# RasberryPi5.net
KiCad netlist of a schematic drawn in Altium Designer
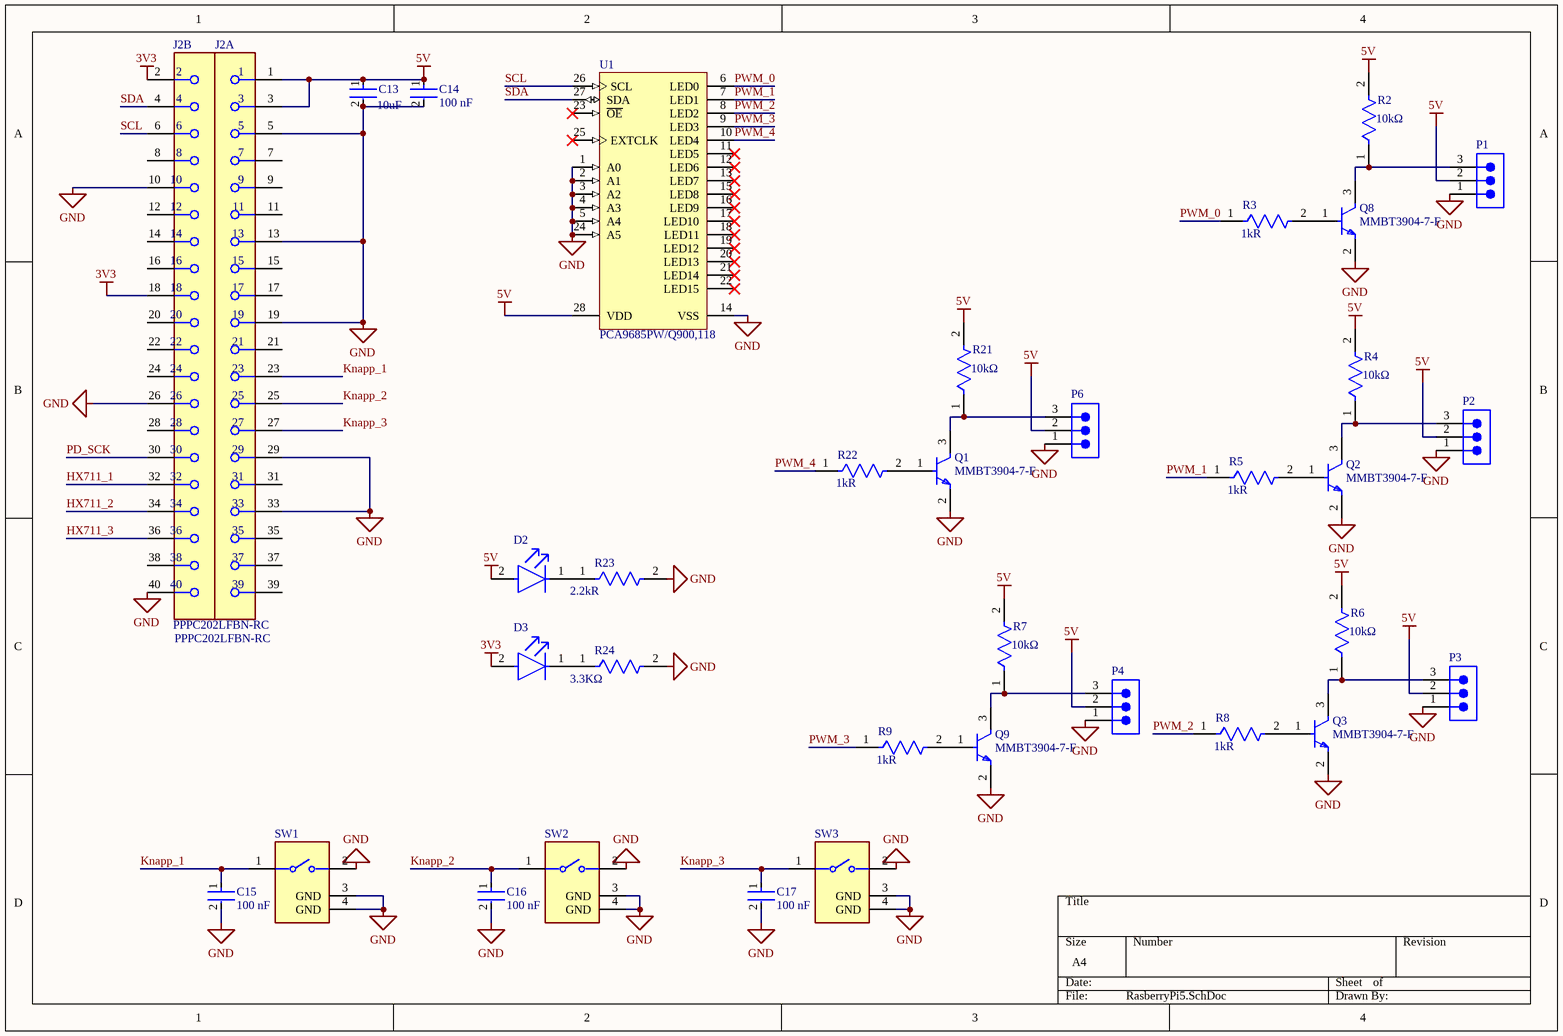
[diagram p0: RasberryPi5.SchDoc]

(export (version "E")
  (design (tool "Eeschema 10.0.6"))
  (components
    (comp (ref "C13")
      (value "10uF")
      (footprint "FP-GRM18-0_15-MFG")
      (description "CAP CER 10UF 10V X5R 0603")
      (fields
        (field (name "OCTOPART") "https://octopart.com/grm188r61a106ke69d-murata-22851381")
        (field (name "MANUFACTURER PART NUMBER") "GRM188R61A106KE69D")
      )
      (libsource (lib "Altium Content Vault") (part "11868f565c42a9108669ba33697ecf6"))
    )
    (comp (ref "C14")
      (value "100 nF")
      (footprint "FP-CC0603-DA-MFG")
      (description "CC0603 100 nF X7R 10.00% 25 V")
      (fields (field (name "VOLTAGE") "25 V") (field (name "MANUFACTURER PART NUMBER") "CC0603KPX7R8BB104"))
      (libsource (lib "Altium Content Vault") (part "11868f565c42a9108669ba33697ecf6"))
    )
    (comp (ref "C15")
      (value "100 nF")
      (footprint "FP-CC0603-DA-MFG")
      (description "CC0603 100 nF X7R 10.00% 25 V")
      (fields (field (name "VOLTAGE") "25 V") (field (name "MANUFACTURER PART NUMBER") "CC0603KPX7R8BB104"))
      (libsource (lib "Altium Content Vault") (part "11868f565c42a9108669ba33697ecf6"))
    )
    (comp (ref "C16")
      (value "100 nF")
      (footprint "FP-CC0603-DA-MFG")
      (description "CC0603 100 nF X7R 10.00% 25 V")
      (fields (field (name "VOLTAGE") "25 V") (field (name "MANUFACTURER PART NUMBER") "CC0603KPX7R8BB104"))
      (libsource (lib "Altium Content Vault") (part "11868f565c42a9108669ba33697ecf6"))
    )
    (comp (ref "C17")
      (value "100 nF")
      (footprint "FP-CC0603-DA-MFG")
      (description "CC0603 100 nF X7R 10.00% 25 V")
      (fields (field (name "VOLTAGE") "25 V") (field (name "MANUFACTURER PART NUMBER") "CC0603KPX7R8BB104"))
      (libsource (lib "Altium Content Vault") (part "11868f565c42a9108669ba33697ecf6"))
    )
    (comp (ref "D2")
      (value "LTST-C193KGKT-5A")
      (footprint "FP-LTST-C193KGKT-5A-MFG")
      (description "LED GREEN CLEAR CHIP SMD")
      (libsource (lib "Altium Content Vault") (part "8706943c75ba83719d021d2fdc84c58"))
    )
    (comp (ref "D3")
      (value "LTST-C193KGKT-5A")
      (footprint "FP-LTST-C193KGKT-5A-MFG")
      (description "LED GREEN CLEAR CHIP SMD")
      (libsource (lib "Altium Content Vault") (part "8706943c75ba83719d021d2fdc84c58"))
    )
    (comp (ref "J2")
      (value "PPPC202LFBN-RC")
      (footprint "FP-PPPC202LFBN-RC-MFG")
      (description "PPPC202LFBN-RC Female, 40C, Straight, .100\"CC; 3.20mm Tail, No Mt.; PBT, Phos Bronze, 105 C")
      (libsource (lib "Altium Content Vault") (part "e49c40d8a4b72700ef4f9e86232dadc"))
    )
    (comp (ref "P1")
      (value "MTSW-103-08-L-S-229-RA")
      (footprint "SMTC-MTSW-103-08-X-S-229-RA")
      (fields (field (name "MANUFACTURER") "Samtec"))
      (libsource (lib "Altium Content Vault") (part "SMTC-MTSW-103-08-X-S-229-RA"))
    )
    (comp (ref "P2")
      (value "MTSW-103-08-L-S-229-RA")
      (footprint "SMTC-MTSW-103-08-X-S-229-RA")
      (fields (field (name "MANUFACTURER") "Samtec"))
      (libsource (lib "Altium Content Vault") (part "SMTC-MTSW-103-08-X-S-229-RA"))
    )
    (comp (ref "P3")
      (value "MTSW-103-08-L-S-229-RA")
      (footprint "SMTC-MTSW-103-08-X-S-229-RA")
      (fields (field (name "MANUFACTURER") "Samtec"))
      (libsource (lib "Altium Content Vault") (part "SMTC-MTSW-103-08-X-S-229-RA"))
    )
    (comp (ref "P4")
      (value "MTSW-103-08-L-S-229-RA")
      (footprint "SMTC-MTSW-103-08-X-S-229-RA")
      (fields (field (name "MANUFACTURER") "Samtec"))
      (libsource (lib "Altium Content Vault") (part "SMTC-MTSW-103-08-X-S-229-RA"))
    )
    (comp (ref "P6")
      (value "MTSW-103-08-L-S-229-RA")
      (footprint "SMTC-MTSW-103-08-X-S-229-RA")
      (fields (field (name "MANUFACTURER") "Samtec"))
      (libsource (lib "Altium Content Vault") (part "SMTC-MTSW-103-08-X-S-229-RA"))
    )
    (comp (ref "Q1")
      (value "MMBT3904-7-F")
      (footprint "FP-SOT23-IPC_A")
      (description "TRANS NPN 40V 0.2A SMD SOT23-3")
      (libsource (lib "Altium Content Vault") (part "b44e953556f554d0102664c7d152cb4"))
    )
    (comp (ref "Q2")
      (value "MMBT3904-7-F")
      (footprint "FP-SOT23-IPC_A")
      (description "TRANS NPN 40V 0.2A SMD SOT23-3")
      (libsource (lib "Altium Content Vault") (part "b44e953556f554d0102664c7d152cb4"))
    )
    (comp (ref "Q3")
      (value "MMBT3904-7-F")
      (footprint "FP-SOT23-IPC_A")
      (description "TRANS NPN 40V 0.2A SMD SOT23-3")
      (libsource (lib "Altium Content Vault") (part "b44e953556f554d0102664c7d152cb4"))
    )
    (comp (ref "Q8")
      (value "MMBT3904-7-F")
      (footprint "FP-SOT23-IPC_A")
      (description "TRANS NPN 40V 0.2A SMD SOT23-3")
      (libsource (lib "Altium Content Vault") (part "b44e953556f554d0102664c7d152cb4"))
    )
    (comp (ref "Q9")
      (value "MMBT3904-7-F")
      (footprint "FP-SOT23-IPC_A")
      (description "TRANS NPN 40V 0.2A SMD SOT23-3")
      (libsource (lib "Altium Content Vault") (part "b44e953556f554d0102664c7d152cb4"))
    )
    (comp (ref "R2")
      (value "SG73P1JTTD1002F")
      (footprint "FP-SG73P1J-MFG")
      (description "SG73P1JTTD1002F Res Thick Film 0603 10K Ohm 1% 0.2W(1/5W) ±100ppm/C Pad SMD Automotive T/R")
      (fields (field (name "TOLERANCE") "1%") (field (name "RESISTANCE") "10kΩ"))
      (libsource (lib "Altium Content Vault") (part "1029c3af85768c4190bb7ad29bc67b5"))
    )
    (comp (ref "R3")
      (value "RK73G1JTTD1001F")
      (footprint "FP-RK73G1J-IPC_B")
      (description "1kΩ ±1% 0.1W Chip Resistor 0603 Thick Film AEC-Q200 Qualified")
      (fields (field (name "RESISTANCE") "1kR") (field (name "TOLERANCE") "1%"))
      (libsource (lib "Altium Content Vault") (part "1029c3af85768c4190bb7ad29bc67b5"))
    )
    (comp (ref "R4")
      (value "SG73P1JTTD1002F")
      (footprint "FP-SG73P1J-MFG")
      (description "SG73P1JTTD1002F Res Thick Film 0603 10K Ohm 1% 0.2W(1/5W) ±100ppm/C Pad SMD Automotive T/R")
      (fields (field (name "TOLERANCE") "1%") (field (name "RESISTANCE") "10kΩ"))
      (libsource (lib "Altium Content Vault") (part "1029c3af85768c4190bb7ad29bc67b5"))
    )
    (comp (ref "R5")
      (value "RK73G1JTTD1001F")
      (footprint "FP-RK73G1J-IPC_B")
      (description "1kΩ ±1% 0.1W Chip Resistor 0603 Thick Film AEC-Q200 Qualified")
      (fields (field (name "RESISTANCE") "1kR") (field (name "TOLERANCE") "1%"))
      (libsource (lib "Altium Content Vault") (part "1029c3af85768c4190bb7ad29bc67b5"))
    )
    (comp (ref "R6")
      (value "SG73P1JTTD1002F")
      (footprint "FP-SG73P1J-MFG")
      (description "SG73P1JTTD1002F Res Thick Film 0603 10K Ohm 1% 0.2W(1/5W) ±100ppm/C Pad SMD Automotive T/R")
      (fields (field (name "TOLERANCE") "1%") (field (name "RESISTANCE") "10kΩ"))
      (libsource (lib "Altium Content Vault") (part "1029c3af85768c4190bb7ad29bc67b5"))
    )
    (comp (ref "R7")
      (value "SG73P1JTTD1002F")
      (footprint "FP-SG73P1J-MFG")
      (description "SG73P1JTTD1002F Res Thick Film 0603 10K Ohm 1% 0.2W(1/5W) ±100ppm/C Pad SMD Automotive T/R")
      (fields (field (name "TOLERANCE") "1%") (field (name "RESISTANCE") "10kΩ"))
      (libsource (lib "Altium Content Vault") (part "1029c3af85768c4190bb7ad29bc67b5"))
    )
    (comp (ref "R8")
      (value "RK73G1JTTD1001F")
      (footprint "FP-RK73G1J-IPC_B")
      (description "1kΩ ±1% 0.1W Chip Resistor 0603 Thick Film AEC-Q200 Qualified")
      (fields (field (name "RESISTANCE") "1kR") (field (name "TOLERANCE") "1%"))
      (libsource (lib "Altium Content Vault") (part "1029c3af85768c4190bb7ad29bc67b5"))
    )
    (comp (ref "R9")
      (value "RK73G1JTTD1001F")
      (footprint "FP-RK73G1J-IPC_B")
      (description "1kΩ ±1% 0.1W Chip Resistor 0603 Thick Film AEC-Q200 Qualified")
      (fields (field (name "RESISTANCE") "1kR") (field (name "TOLERANCE") "1%"))
      (libsource (lib "Altium Content Vault") (part "1029c3af85768c4190bb7ad29bc67b5"))
    )
    (comp (ref "R21")
      (value "SG73P1JTTD1002F")
      (footprint "FP-SG73P1J-MFG")
      (description "SG73P1JTTD1002F Res Thick Film 0603 10K Ohm 1% 0.2W(1/5W) ±100ppm/C Pad SMD Automotive T/R")
      (fields (field (name "TOLERANCE") "1%") (field (name "RESISTANCE") "10kΩ"))
      (libsource (lib "Altium Content Vault") (part "1029c3af85768c4190bb7ad29bc67b5"))
    )
    (comp (ref "R22")
      (value "RK73G1JTTD1001F")
      (footprint "FP-RK73G1J-IPC_B")
      (description "1kΩ ±1% 0.1W Chip Resistor 0603 Thick Film AEC-Q200 Qualified")
      (fields (field (name "RESISTANCE") "1kR") (field (name "TOLERANCE") "1%"))
      (libsource (lib "Altium Content Vault") (part "1029c3af85768c4190bb7ad29bc67b5"))
    )
    (comp (ref "R23")
      (value "RC1608J222CS")
      (footprint "FP-RC1608-IPC_C")
      (description "Res Thick Film 0603 2.2kΩ 5% 0.1W ±100ppm/°C Molded SMD T/R")
      (fields (field (name "RESISTANCE") "2.2kR") (field (name "TOLERANCE") "5%"))
      (libsource (lib "Altium Content Vault") (part "1029c3af85768c4190bb7ad29bc67b5"))
    )
    (comp (ref "R24")
      (value "3.3KΩ")
      (footprint "FP-CRGCQ0603-IPC_C")
      (description "CRGCQ 0603 3K3 5%")
      (fields (field (name "TOLERANCE") "0.05") (field (name "MANUFACTURER") "TE Connectivity"))
      (libsource (lib "Altium Content Vault") (part "1029c3af85768c4190bb7ad29bc67b5"))
    )
    (comp (ref "SW1")
      (value "B3F-3122")
      (footprint "FP-B3F-3122-MFG")
      (description "SWITCH TACTILE SPST-NO 0.05A 24V")
      (libsource (lib "Altium Content Vault") (part "05c531d4b500f7e9514fa3f65f375ae"))
    )
    (comp (ref "SW2")
      (value "B3F-3122")
      (footprint "FP-B3F-3122-MFG")
      (description "SWITCH TACTILE SPST-NO 0.05A 24V")
      (libsource (lib "Altium Content Vault") (part "05c531d4b500f7e9514fa3f65f375ae"))
    )
    (comp (ref "SW3")
      (value "B3F-3122")
      (footprint "FP-B3F-3122-MFG")
      (description "SWITCH TACTILE SPST-NO 0.05A 24V")
      (libsource (lib "Altium Content Vault") (part "05c531d4b500f7e9514fa3f65f375ae"))
    )
    (comp (ref "U1")
      (value "PCA9685PW/Q900,118")
      (footprint "SOT361-1_V")
      (fields (field (name "PARTNUMBER") "PCA9685"))
      (libsource (lib "Altium Content Vault") (part "NXP-PCA9685-SOT361-1"))
    )
  )
  (nets
    (net (code "1") (name "/HX711_1") (class "Default")
      (node (ref "J2") (pin "32") (pinfunction "32_32") (pintype "passive"))
    )
    (net (code "2") (name "/HX711_2") (class "Default")
      (node (ref "J2") (pin "34") (pinfunction "34_34") (pintype "passive"))
    )
    (net (code "3") (name "/HX711_3") (class "Default")
      (node (ref "J2") (pin "36") (pinfunction "36_36") (pintype "passive"))
    )
    (net (code "4") (name "/Knapp_1") (class "Default")
      (node (ref "C15") (pin "1") (pinfunction "1_1") (pintype "passive"))
      (node (ref "J2") (pin "23") (pinfunction "23_23") (pintype "passive"))
      (node (ref "SW1") (pin "1") (pinfunction "1_1") (pintype "passive"))
    )
    (net (code "5") (name "/Knapp_2") (class "Default")
      (node (ref "C16") (pin "1") (pinfunction "1_1") (pintype "passive"))
      (node (ref "J2") (pin "25") (pinfunction "25_25") (pintype "passive"))
      (node (ref "SW2") (pin "1") (pinfunction "1_1") (pintype "passive"))
    )
    (net (code "6") (name "/Knapp_3") (class "Default")
      (node (ref "C17") (pin "1") (pinfunction "1_1") (pintype "passive"))
      (node (ref "J2") (pin "27") (pinfunction "27_27") (pintype "passive"))
      (node (ref "SW3") (pin "1") (pinfunction "1_1") (pintype "passive"))
    )
    (net (code "7") (name "/PD_SCK") (class "Default")
      (node (ref "J2") (pin "30") (pinfunction "30_30") (pintype "passive"))
    )
    (net (code "8") (name "/PWM_0") (class "Default")
      (node (ref "R3") (pin "1") (pinfunction "1_1") (pintype "passive"))
      (node (ref "U1") (pin "6") (pinfunction "LED0_6") (pintype "tri_state"))
    )
    (net (code "9") (name "/PWM_1") (class "Default")
      (node (ref "R5") (pin "1") (pinfunction "1_1") (pintype "passive"))
      (node (ref "U1") (pin "7") (pinfunction "LED1_7") (pintype "tri_state"))
    )
    (net (code "10") (name "/PWM_2") (class "Default")
      (node (ref "R8") (pin "1") (pinfunction "1_1") (pintype "passive"))
      (node (ref "U1") (pin "8") (pinfunction "LED2_8") (pintype "tri_state"))
    )
    (net (code "11") (name "/PWM_3") (class "Default")
      (node (ref "R9") (pin "1") (pinfunction "1_1") (pintype "passive"))
      (node (ref "U1") (pin "9") (pinfunction "LED3_9") (pintype "tri_state"))
    )
    (net (code "12") (name "/PWM_4") (class "Default")
      (node (ref "R22") (pin "1") (pinfunction "1_1") (pintype "passive"))
      (node (ref "U1") (pin "10") (pinfunction "LED4_10") (pintype "tri_state"))
    )
    (net (code "13") (name "/SCL") (class "Default")
      (node (ref "J2") (pin "6") (pinfunction "6_6") (pintype "passive"))
      (node (ref "U1") (pin "26") (pinfunction "SCL_26") (pintype "input"))
    )
    (net (code "14") (name "/SDA") (class "Default")
      (node (ref "J2") (pin "4") (pinfunction "4_4") (pintype "passive"))
      (node (ref "U1") (pin "27") (pinfunction "SDA_27") (pintype "bidirectional"))
    )
    (net (code "15") (name "3V3") (class "Default")
      (node (ref "D3") (pin "2") (pinfunction "A_2") (pintype "passive"))
      (node (ref "J2") (pin "18") (pinfunction "18_18") (pintype "passive"))
      (node (ref "J2") (pin "2") (pinfunction "2_2") (pintype "passive"))
    )
    (net (code "16") (name "5V") (class "Default")
      (node (ref "C13") (pin "1") (pinfunction "1_1") (pintype "passive"))
      (node (ref "C14") (pin "1") (pinfunction "1_1") (pintype "passive"))
      (node (ref "D2") (pin "2") (pinfunction "A_2") (pintype "passive"))
      (node (ref "J2") (pin "1") (pinfunction "1_1") (pintype "passive"))
      (node (ref "J2") (pin "3") (pinfunction "3_3") (pintype "passive"))
      (node (ref "P1") (pin "2") (pinfunction "2_2") (pintype "passive"))
      (node (ref "P2") (pin "2") (pinfunction "2_2") (pintype "passive"))
      (node (ref "P3") (pin "2") (pinfunction "2_2") (pintype "passive"))
      (node (ref "P4") (pin "2") (pinfunction "2_2") (pintype "passive"))
      (node (ref "P6") (pin "2") (pinfunction "2_2") (pintype "passive"))
      (node (ref "R2") (pin "2") (pinfunction "2_2") (pintype "passive"))
      (node (ref "R21") (pin "2") (pinfunction "2_2") (pintype "passive"))
      (node (ref "R4") (pin "2") (pinfunction "2_2") (pintype "passive"))
      (node (ref "R6") (pin "2") (pinfunction "2_2") (pintype "passive"))
      (node (ref "R7") (pin "2") (pinfunction "2_2") (pintype "passive"))
      (node (ref "U1") (pin "28") (pinfunction "VDD_28") (pintype "power_in"))
    )
    (net (code "17") (name "GND") (class "Default")
      (node (ref "C13") (pin "2") (pinfunction "2_2") (pintype "passive"))
      (node (ref "C14") (pin "2") (pinfunction "2_2") (pintype "passive"))
      (node (ref "C15") (pin "2") (pinfunction "2_2") (pintype "passive"))
      (node (ref "C16") (pin "2") (pinfunction "2_2") (pintype "passive"))
      (node (ref "C17") (pin "2") (pinfunction "2_2") (pintype "passive"))
      (node (ref "J2") (pin "10") (pinfunction "10_10") (pintype "passive"))
      (node (ref "J2") (pin "13") (pinfunction "13_13") (pintype "passive"))
      (node (ref "J2") (pin "19") (pinfunction "19_19") (pintype "passive"))
      (node (ref "J2") (pin "26") (pinfunction "26_26") (pintype "passive"))
      (node (ref "J2") (pin "29") (pinfunction "29_29") (pintype "passive"))
      (node (ref "J2") (pin "33") (pinfunction "33_33") (pintype "passive"))
      (node (ref "J2") (pin "40") (pinfunction "40_40") (pintype "passive"))
      (node (ref "J2") (pin "5") (pinfunction "5_5") (pintype "passive"))
      (node (ref "P1") (pin "1") (pinfunction "1_1") (pintype "passive"))
      (node (ref "P2") (pin "1") (pinfunction "1_1") (pintype "passive"))
      (node (ref "P3") (pin "1") (pinfunction "1_1") (pintype "passive"))
      (node (ref "P4") (pin "1") (pinfunction "1_1") (pintype "passive"))
      (node (ref "P6") (pin "1") (pinfunction "1_1") (pintype "passive"))
      (node (ref "Q1") (pin "2") (pinfunction "E_2") (pintype "passive"))
      (node (ref "Q2") (pin "2") (pinfunction "E_2") (pintype "passive"))
      (node (ref "Q3") (pin "2") (pinfunction "E_2") (pintype "passive"))
      (node (ref "Q8") (pin "2") (pinfunction "E_2") (pintype "passive"))
      (node (ref "Q9") (pin "2") (pinfunction "E_2") (pintype "passive"))
      (node (ref "R23") (pin "2") (pinfunction "2_2") (pintype "passive"))
      (node (ref "R24") (pin "2") (pinfunction "2_2") (pintype "passive"))
      (node (ref "SW1") (pin "2") (pinfunction "2_2") (pintype "passive"))
      (node (ref "SW1") (pin "3") (pinfunction "GND_3") (pintype "power_in"))
      (node (ref "SW1") (pin "4") (pinfunction "GND_4") (pintype "power_in"))
      (node (ref "SW2") (pin "2") (pinfunction "2_2") (pintype "passive"))
      (node (ref "SW2") (pin "3") (pinfunction "GND_3") (pintype "power_in"))
      (node (ref "SW2") (pin "4") (pinfunction "GND_4") (pintype "power_in"))
      (node (ref "SW3") (pin "2") (pinfunction "2_2") (pintype "passive"))
      (node (ref "SW3") (pin "3") (pinfunction "GND_3") (pintype "power_in"))
      (node (ref "SW3") (pin "4") (pinfunction "GND_4") (pintype "power_in"))
      (node (ref "U1") (pin "1") (pinfunction "A0_1") (pintype "input"))
      (node (ref "U1") (pin "14") (pinfunction "VSS_14") (pintype "power_in"))
      (node (ref "U1") (pin "2") (pinfunction "A1_2") (pintype "input"))
      (node (ref "U1") (pin "24") (pinfunction "A5_24") (pintype "input"))
      (node (ref "U1") (pin "3") (pinfunction "A2_3") (pintype "input"))
      (node (ref "U1") (pin "4") (pinfunction "A3_4") (pintype "input"))
      (node (ref "U1") (pin "5") (pinfunction "A4_5") (pintype "input"))
    )
    (net (code "18") (name "Net-(D2-C)") (class "Default")
      (node (ref "D2") (pin "1") (pinfunction "C_1") (pintype "passive"))
      (node (ref "R23") (pin "1") (pinfunction "1_1") (pintype "passive"))
    )
    (net (code "19") (name "Net-(D3-C)") (class "Default")
      (node (ref "D3") (pin "1") (pinfunction "C_1") (pintype "passive"))
      (node (ref "R24") (pin "1") (pinfunction "1_1") (pintype "passive"))
    )
    (net (code "20") (name "Net-(Q1-B)") (class "Default")
      (node (ref "Q1") (pin "1") (pinfunction "B_1") (pintype "passive"))
      (node (ref "R22") (pin "2") (pinfunction "2_2") (pintype "passive"))
    )
    (net (code "21") (name "Net-(Q1-C)") (class "Default")
      (node (ref "P6") (pin "3") (pinfunction "3_3") (pintype "passive"))
      (node (ref "Q1") (pin "3") (pinfunction "C_3") (pintype "passive"))
      (node (ref "R21") (pin "1") (pinfunction "1_1") (pintype "passive"))
    )
    (net (code "22") (name "Net-(Q2-B)") (class "Default")
      (node (ref "Q2") (pin "1") (pinfunction "B_1") (pintype "passive"))
      (node (ref "R5") (pin "2") (pinfunction "2_2") (pintype "passive"))
    )
    (net (code "23") (name "Net-(Q2-C)") (class "Default")
      (node (ref "P2") (pin "3") (pinfunction "3_3") (pintype "passive"))
      (node (ref "Q2") (pin "3") (pinfunction "C_3") (pintype "passive"))
      (node (ref "R4") (pin "1") (pinfunction "1_1") (pintype "passive"))
    )
    (net (code "24") (name "Net-(Q3-B)") (class "Default")
      (node (ref "Q3") (pin "1") (pinfunction "B_1") (pintype "passive"))
      (node (ref "R8") (pin "2") (pinfunction "2_2") (pintype "passive"))
    )
    (net (code "25") (name "Net-(Q3-C)") (class "Default")
      (node (ref "P3") (pin "3") (pinfunction "3_3") (pintype "passive"))
      (node (ref "Q3") (pin "3") (pinfunction "C_3") (pintype "passive"))
      (node (ref "R6") (pin "1") (pinfunction "1_1") (pintype "passive"))
    )
    (net (code "26") (name "Net-(Q8-B)") (class "Default")
      (node (ref "Q8") (pin "1") (pinfunction "B_1") (pintype "passive"))
      (node (ref "R3") (pin "2") (pinfunction "2_2") (pintype "passive"))
    )
    (net (code "27") (name "Net-(Q8-C)") (class "Default")
      (node (ref "P1") (pin "3") (pinfunction "3_3") (pintype "passive"))
      (node (ref "Q8") (pin "3") (pinfunction "C_3") (pintype "passive"))
      (node (ref "R2") (pin "1") (pinfunction "1_1") (pintype "passive"))
    )
    (net (code "28") (name "Net-(Q9-B)") (class "Default")
      (node (ref "Q9") (pin "1") (pinfunction "B_1") (pintype "passive"))
      (node (ref "R9") (pin "2") (pinfunction "2_2") (pintype "passive"))
    )
    (net (code "29") (name "Net-(Q9-C)") (class "Default")
      (node (ref "P4") (pin "3") (pinfunction "3_3") (pintype "passive"))
      (node (ref "Q9") (pin "3") (pinfunction "C_3") (pintype "passive"))
      (node (ref "R7") (pin "1") (pinfunction "1_1") (pintype "passive"))
    )
    (net (code "30") (name "unconnected-(J2-Pad7)") (class "Default")
      (node (ref "J2") (pin "7") (pinfunction "7_7") (pintype "passive"))
    )
    (net (code "31") (name "unconnected-(J2-Pad8)") (class "Default")
      (node (ref "J2") (pin "8") (pinfunction "8_8") (pintype "passive"))
    )
    (net (code "32") (name "unconnected-(J2-Pad9)") (class "Default")
      (node (ref "J2") (pin "9") (pinfunction "9_9") (pintype "passive"))
    )
    (net (code "33") (name "unconnected-(J2-Pad11)") (class "Default")
      (node (ref "J2") (pin "11") (pinfunction "11_11") (pintype "passive"))
    )
    (net (code "34") (name "unconnected-(J2-Pad12)") (class "Default")
      (node (ref "J2") (pin "12") (pinfunction "12_12") (pintype "passive"))
    )
    (net (code "35") (name "unconnected-(J2-Pad14)") (class "Default")
      (node (ref "J2") (pin "14") (pinfunction "14_14") (pintype "passive"))
    )
    (net (code "36") (name "unconnected-(J2-Pad15)") (class "Default")
      (node (ref "J2") (pin "15") (pinfunction "15_15") (pintype "passive"))
    )
    (net (code "37") (name "unconnected-(J2-Pad16)") (class "Default")
      (node (ref "J2") (pin "16") (pinfunction "16_16") (pintype "passive"))
    )
    (net (code "38") (name "unconnected-(J2-Pad17)") (class "Default")
      (node (ref "J2") (pin "17") (pinfunction "17_17") (pintype "passive"))
    )
    (net (code "39") (name "unconnected-(J2-Pad20)") (class "Default")
      (node (ref "J2") (pin "20") (pinfunction "20_20") (pintype "passive"))
    )
    (net (code "40") (name "unconnected-(J2-Pad21)") (class "Default")
      (node (ref "J2") (pin "21") (pinfunction "21_21") (pintype "passive"))
    )
    (net (code "41") (name "unconnected-(J2-Pad22)") (class "Default")
      (node (ref "J2") (pin "22") (pinfunction "22_22") (pintype "passive"))
    )
    (net (code "42") (name "unconnected-(J2-Pad24)") (class "Default")
      (node (ref "J2") (pin "24") (pinfunction "24_24") (pintype "passive"))
    )
    (net (code "43") (name "unconnected-(J2-Pad28)") (class "Default")
      (node (ref "J2") (pin "28") (pinfunction "28_28") (pintype "passive"))
    )
    (net (code "44") (name "unconnected-(J2-Pad31)") (class "Default")
      (node (ref "J2") (pin "31") (pinfunction "31_31") (pintype "passive"))
    )
    (net (code "45") (name "unconnected-(J2-Pad35)") (class "Default")
      (node (ref "J2") (pin "35") (pinfunction "35_35") (pintype "passive"))
    )
    (net (code "46") (name "unconnected-(J2-Pad37)") (class "Default")
      (node (ref "J2") (pin "37") (pinfunction "37_37") (pintype "passive"))
    )
    (net (code "47") (name "unconnected-(J2-Pad38)") (class "Default")
      (node (ref "J2") (pin "38") (pinfunction "38_38") (pintype "passive"))
    )
    (net (code "48") (name "unconnected-(J2-Pad39)") (class "Default")
      (node (ref "J2") (pin "39") (pinfunction "39_39") (pintype "passive"))
    )
    (net (code "49") (name "unconnected-(U1-EXTCLK-Pad25)") (class "Default")
      (node (ref "U1") (pin "25") (pinfunction "EXTCLK_25") (pintype "input+no_connect"))
    )
    (net (code "50") (name "unconnected-(U1-LED5-Pad11)") (class "Default")
      (node (ref "U1") (pin "11") (pinfunction "LED5_11") (pintype "tri_state+no_connect"))
    )
    (net (code "51") (name "unconnected-(U1-LED6-Pad12)") (class "Default")
      (node (ref "U1") (pin "12") (pinfunction "LED6_12") (pintype "tri_state+no_connect"))
    )
    (net (code "52") (name "unconnected-(U1-LED7-Pad13)") (class "Default")
      (node (ref "U1") (pin "13") (pinfunction "LED7_13") (pintype "tri_state+no_connect"))
    )
    (net (code "53") (name "unconnected-(U1-LED8-Pad15)") (class "Default")
      (node (ref "U1") (pin "15") (pinfunction "LED8_15") (pintype "tri_state+no_connect"))
    )
    (net (code "54") (name "unconnected-(U1-LED9-Pad16)") (class "Default")
      (node (ref "U1") (pin "16") (pinfunction "LED9_16") (pintype "tri_state+no_connect"))
    )
    (net (code "55") (name "unconnected-(U1-LED10-Pad17)") (class "Default")
      (node (ref "U1") (pin "17") (pinfunction "LED10_17") (pintype "tri_state+no_connect"))
    )
    (net (code "56") (name "unconnected-(U1-LED11-Pad18)") (class "Default")
      (node (ref "U1") (pin "18") (pinfunction "LED11_18") (pintype "tri_state+no_connect"))
    )
    (net (code "57") (name "unconnected-(U1-LED12-Pad19)") (class "Default")
      (node (ref "U1") (pin "19") (pinfunction "LED12_19") (pintype "tri_state+no_connect"))
    )
    (net (code "58") (name "unconnected-(U1-LED13-Pad20)") (class "Default")
      (node (ref "U1") (pin "20") (pinfunction "LED13_20") (pintype "tri_state+no_connect"))
    )
    (net (code "59") (name "unconnected-(U1-LED14-Pad21)") (class "Default")
      (node (ref "U1") (pin "21") (pinfunction "LED14_21") (pintype "tri_state+no_connect"))
    )
    (net (code "60") (name "unconnected-(U1-LED15-Pad22)") (class "Default")
      (node (ref "U1") (pin "22") (pinfunction "LED15_22") (pintype "tri_state+no_connect"))
    )
    (net (code "61") (name "unconnected-(U1-~{OE}-Pad23)") (class "Default")
      (node (ref "U1") (pin "23") (pinfunction "~{OE}_23") (pintype "input+no_connect"))
    )
  )
)
